# 3V3.net
KiCad netlist of a schematic drawn in Altium Designer
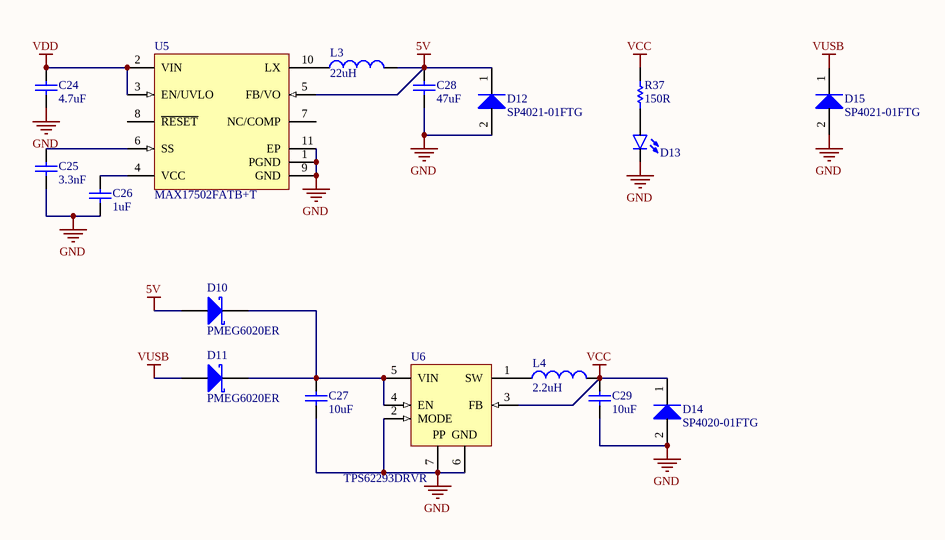
[diagram p0: 3V3.SchDoc]

(export (version "E")
  (design (tool "Eeschema 10.0.6"))
  (components
    (comp (ref "C24")
      (value "4.7uF")
      (footprint "C1210[3225X200]")
      (description "4.7uF 100V 10% 1210 (3225 Metric)")
      (fields (field (name "TOLERANCE") "10%") (field (name "PARTNUMBER") "GRJ32DC72A475KE11L"))
      (libsource (lib "Capacitors") (part "CAP_4.7uF_100V_1210_10%"))
    )
    (comp (ref "C25")
      (value "3.3nF")
      (footprint "C0402[1005X55]")
      (description "3.3nF 50V 10% 0402 (1005 Metric)")
      (fields (field (name "TOLERANCE") "10%") (field (name "PARTNUMBER") "GRM155R71H332KA01D"))
      (libsource (lib "Capacitors") (part "CAP_3.3nF_50V_0402_10%"))
    )
    (comp (ref "C26")
      (value "1uF")
      (footprint "C0402[1005X55]")
      (description "1uF 6.3V 10% 0402 (1005 Metric)")
      (fields (field (name "TOLERANCE") "10%") (field (name "PARTNUMBER") "GRM155R70J105KA12D"))
      (libsource (lib "Capacitors") (part "CAP_1uF_6.3V_0402_10%"))
    )
    (comp (ref "C27")
      (value "10uF")
      (footprint "C0402[1005X55]")
      (description "10uF 6.3V 20% 0402 (1005 Metric)")
      (fields (field (name "TOLERANCE") "20%") (field (name "PARTNUMBER") "GRM155R60J106ME44D"))
      (libsource (lib "Capacitors") (part "CAP_10uF_6.3V_0402_20%"))
    )
    (comp (ref "C28")
      (value "47uF")
      (footprint "C1210[3225X250]")
      (description "47uF 6.3V 10% 1210 (3225 Metric)")
      (fields (field (name "TOLERANCE") "10%") (field (name "PARTNUMBER") "GRM32ER70J476KE20L"))
      (libsource (lib "Capacitors") (part "CAP_47uF_6.3V_1210_10%"))
    )
    (comp (ref "C29")
      (value "10uF")
      (footprint "C0402[1005X55]")
      (description "10uF 6.3V 20% 0402 (1005 Metric)")
      (fields (field (name "TOLERANCE") "20%") (field (name "PARTNUMBER") "GRM155R60J106ME44D"))
      (libsource (lib "Capacitors") (part "CAP_10uF_6.3V_0402_20%"))
    )
    (comp (ref "D10")
      (value "PMEG6020ER")
      (footprint "SOD-123")
      (fields (field (name "PARTNUMBER") "PMEG6020ER,115") (field (name "MANUFACTURER") "NXP Semiconductors"))
      (libsource (lib "Diodes") (part "PMEG6020ER"))
    )
    (comp (ref "D11")
      (value "PMEG6020ER")
      (footprint "SOD-123")
      (fields (field (name "PARTNUMBER") "PMEG6020ER,115") (field (name "MANUFACTURER") "NXP Semiconductors"))
      (libsource (lib "Diodes") (part "PMEG6020ER"))
    )
    (comp (ref "D12")
      (value "SP4021-01FTG")
      (footprint "SOD-323")
      (fields (field (name "MANUFACTURER") "Littelfuse"))
      (libsource (lib "Diodes") (part "SP4021-01FTG"))
    )
    (comp (ref "D13")
      (value "LED_0603_GREEN_5mA")
      (footprint "LED0603")
      (fields (field (name "PARTNUMBER") "LTST-C193TGKT-5A") (field (name "MANUFACTURER") "Lite-On Inc."))
      (libsource (lib "LEDs") (part "LED_0603_GREEN_5mA"))
    )
    (comp (ref "D14")
      (value "SP4020-01FTG")
      (footprint "SOD323")
      (fields (field (name "MANUFACTURER") "Littelfuse"))
      (libsource (lib "Diodes") (part "SP4020-01FTG"))
    )
    (comp (ref "D15")
      (value "SP4021-01FTG")
      (footprint "SOD-323")
      (fields (field (name "MANUFACTURER") "Littelfuse"))
      (libsource (lib "Diodes-TVS") (part "SP4021-01FTG"))
    )
    (comp (ref "L3")
      (value "22uH")
      (footprint "SDR0604")
      (description "22uH 30% 1.1A 0604")
      (fields (field (name "PARTNUMBER") "SDR0604-220YL") (field (name "MANUFACTURER") "Bourns"))
      (libsource (lib "Inductors") (part "SDR0604-220YL"))
    )
    (comp (ref "L4")
      (value "2.2uH")
      (footprint "IND0805")
      (description "2.2uH 20% 1.7A 0805")
      (fields (field (name "PARTNUMBER") "LQM21PN2R2MGHL") (field (name "MANUFACTURER") "Murata"))
      (libsource (lib "Inductors") (part "IND_2.2uH_1.7A_0805_20%"))
    )
    (comp (ref "R37")
      (value "150R")
      (footprint "R0402[1005]")
      (description "150R 0.063W 1% 0402 (1005 Metric)")
      (fields (field (name "POWER") "0.063W") (field (name "TOLERANCE") "1%"))
      (libsource (lib "Resistors") (part "RES_150R_0402_1%"))
    )
    (comp (ref "U5")
      (value "MAX17502FATB+T")
      (footprint "TDFN-10-EP")
      (fields (field (name "MANUFACTURER") "Maxim Integrated"))
      (libsource (lib "ICs") (part "MAX17502FATB+T"))
    )
    (comp (ref "U6")
      (value "TPS62293DRVR")
      (footprint "WSON-6")
      (description "Voltage Regulators - Switching Regulators 2.25MHz 1A Step-Down Cnvrtr")
      (fields (field (name "MANUFACTURER") "Texas Instruments"))
      (libsource (lib "ICs") (part "TPS62293DRVR"))
    )
  )
  (nets
    (net (code "1") (name "5V") (class "Default")
      (node (ref "C28") (pin "2") (pinfunction "2_2") (pintype "passive"))
      (node (ref "D10") (pin "2") (pinfunction "A_2") (pintype "passive"))
      (node (ref "D12") (pin "1") (pinfunction "K_1") (pintype "passive"))
      (node (ref "L3") (pin "2") (pinfunction "2_2") (pintype "passive"))
      (node (ref "U5") (pin "5") (pinfunction "FB/VO_5") (pintype "input"))
    )
    (net (code "2") (name "GND") (class "Default")
      (node (ref "C24") (pin "1") (pinfunction "1_1") (pintype "passive"))
      (node (ref "C25") (pin "1") (pinfunction "1_1") (pintype "passive"))
      (node (ref "C26") (pin "1") (pinfunction "1_1") (pintype "passive"))
      (node (ref "C27") (pin "1") (pinfunction "1_1") (pintype "passive"))
      (node (ref "C28") (pin "1") (pinfunction "1_1") (pintype "passive"))
      (node (ref "C29") (pin "1") (pinfunction "1_1") (pintype "passive"))
      (node (ref "D12") (pin "2") (pinfunction "A_2") (pintype "passive"))
      (node (ref "D13") (pin "C") (pinfunction "C_C") (pintype "passive"))
      (node (ref "D14") (pin "2") (pinfunction "A_2") (pintype "passive"))
      (node (ref "D15") (pin "2") (pinfunction "A_2") (pintype "passive"))
      (node (ref "U5") (pin "1") (pinfunction "PGND_1") (pintype "power_in"))
      (node (ref "U5") (pin "11") (pinfunction "EP_11") (pintype "power_in"))
      (node (ref "U5") (pin "9") (pinfunction "GND_9") (pintype "power_in"))
      (node (ref "U6") (pin "2") (pinfunction "MODE_2") (pintype "input"))
      (node (ref "U6") (pin "6") (pinfunction "GND_6") (pintype "power_in"))
      (node (ref "U6") (pin "7") (pinfunction "EP_7") (pintype "passive"))
    )
    (net (code "3") (name "Net-(D10-K)") (class "Default")
      (node (ref "C27") (pin "2") (pinfunction "2_2") (pintype "passive"))
      (node (ref "D10") (pin "1") (pinfunction "K_1") (pintype "passive"))
      (node (ref "D11") (pin "1") (pinfunction "K_1") (pintype "passive"))
      (node (ref "U6") (pin "4") (pinfunction "EN_4") (pintype "input"))
      (node (ref "U6") (pin "5") (pinfunction "VIN_5") (pintype "power_in"))
    )
    (net (code "4") (name "Net-(D13-PadA)") (class "Default")
      (node (ref "D13") (pin "A") (pinfunction "A_A") (pintype "passive"))
      (node (ref "R37") (pin "1") (pinfunction "1_1") (pintype "passive"))
    )
    (net (code "5") (name "Net-(U5-LX)") (class "Default")
      (node (ref "L3") (pin "1") (pinfunction "1_1") (pintype "passive"))
      (node (ref "U5") (pin "10") (pinfunction "LX_10") (pintype "passive"))
    )
    (net (code "6") (name "Net-(U5-SS)") (class "Default")
      (node (ref "C25") (pin "2") (pinfunction "2_2") (pintype "passive"))
      (node (ref "U5") (pin "6") (pinfunction "SS_6") (pintype "input"))
    )
    (net (code "7") (name "Net-(U5-VCC)") (class "Default")
      (node (ref "C26") (pin "2") (pinfunction "2_2") (pintype "passive"))
      (node (ref "U5") (pin "4") (pinfunction "VCC_4") (pintype "power_in"))
    )
    (net (code "8") (name "Net-(U6-SW)") (class "Default")
      (node (ref "L4") (pin "1") (pinfunction "1_1") (pintype "passive"))
      (node (ref "U6") (pin "1") (pinfunction "SW_1") (pintype "power_in"))
    )
    (net (code "9") (name "VCC") (class "Default")
      (node (ref "C29") (pin "2") (pinfunction "2_2") (pintype "passive"))
      (node (ref "D14") (pin "1") (pinfunction "K_1") (pintype "passive"))
      (node (ref "L4") (pin "2") (pinfunction "2_2") (pintype "passive"))
      (node (ref "R37") (pin "2") (pinfunction "2_2") (pintype "passive"))
      (node (ref "U6") (pin "3") (pinfunction "FB_3") (pintype "input"))
    )
    (net (code "10") (name "VDD") (class "Default")
      (node (ref "C24") (pin "2") (pinfunction "2_2") (pintype "passive"))
      (node (ref "U5") (pin "2") (pinfunction "VIN_2") (pintype "power_in"))
      (node (ref "U5") (pin "3") (pinfunction "EN/UVLO_3") (pintype "input"))
    )
    (net (code "11") (name "VUSB") (class "Default")
      (node (ref "D11") (pin "2") (pinfunction "A_2") (pintype "passive"))
      (node (ref "D15") (pin "1") (pinfunction "K_1") (pintype "passive"))
    )
    (net (code "12") (name "unconnected-(U5-NC{slash}COMP-Pad7)") (class "Default")
      (node (ref "U5") (pin "7") (pinfunction "NC/COMP_7") (pintype "passive"))
    )
    (net (code "13") (name "unconnected-(U5-~{RESET}-Pad8)") (class "Default")
      (node (ref "U5") (pin "8") (pinfunction "~{RESET}_8") (pintype "open_collector"))
    )
  )
)
